# 10BASE-T1L_3.net
KiCad netlist of a schematic drawn in EAGLE
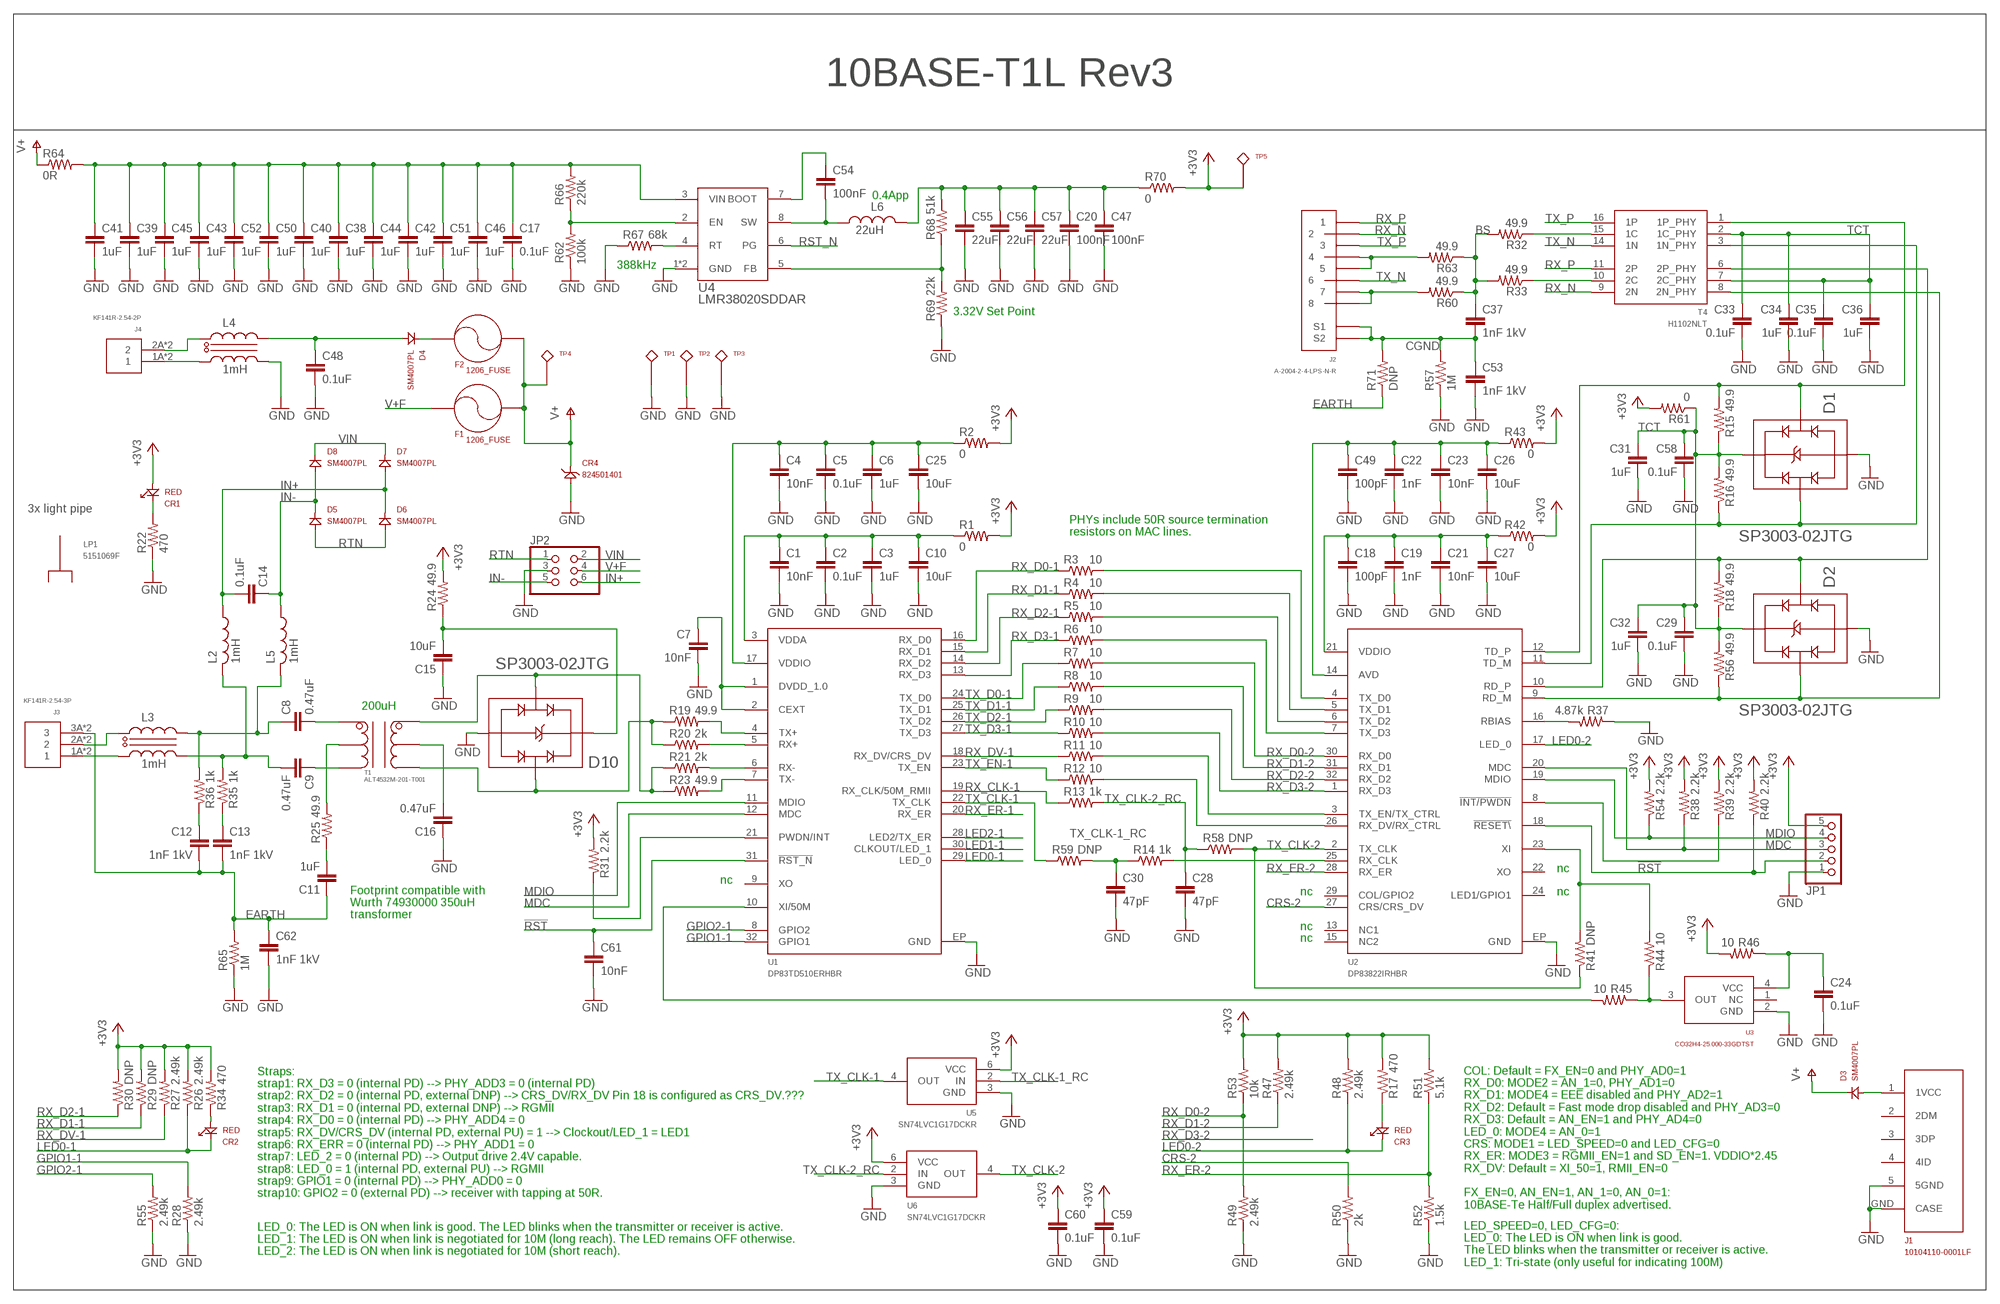
[diagram p0: schematic, sheet 1]

(export (version "E")
  (design (tool "Eeschema 10.0.6"))
  (components
    (comp (ref "C1")
      (value "10nF")
      (footprint "eagle-import:0402_INDUCTOR")
      (libsource (lib "eagle-import") (part "0402_CAPACITOR"))
    )
    (comp (ref "C2")
      (value "0.1uF")
      (footprint "eagle-import:0402_INDUCTOR")
      (libsource (lib "eagle-import") (part "0402_CAPACITOR"))
    )
    (comp (ref "C3")
      (value "1uF")
      (footprint "eagle-import:0402_INDUCTOR")
      (libsource (lib "eagle-import") (part "0402_CAPACITOR"))
    )
    (comp (ref "C4")
      (value "10nF")
      (footprint "eagle-import:0402_INDUCTOR")
      (libsource (lib "eagle-import") (part "0402_CAPACITOR"))
    )
    (comp (ref "C5")
      (value "0.1uF")
      (footprint "eagle-import:0402_INDUCTOR")
      (libsource (lib "eagle-import") (part "0402_CAPACITOR"))
    )
    (comp (ref "C6")
      (value "1uF")
      (footprint "eagle-import:0402_INDUCTOR")
      (libsource (lib "eagle-import") (part "0402_CAPACITOR"))
    )
    (comp (ref "C7")
      (value "10nF")
      (footprint "eagle-import:0402_INDUCTOR")
      (libsource (lib "eagle-import") (part "0402_CAPACITOR"))
    )
    (comp (ref "C8")
      (value "0.47uF")
      (footprint "eagle-import:0603")
      (libsource (lib "eagle-import") (part "0603_CAPACITOR"))
    )
    (comp (ref "C9")
      (value "0.47uF")
      (footprint "eagle-import:0603")
      (libsource (lib "eagle-import") (part "0603_CAPACITOR"))
    )
    (comp (ref "C10")
      (value "10uF")
      (footprint "eagle-import:0603")
      (libsource (lib "eagle-import") (part "0603_CAPACITOR"))
    )
    (comp (ref "C11")
      (value "1uF")
      (footprint "eagle-import:0603")
      (libsource (lib "eagle-import") (part "0603_CAPACITOR"))
    )
    (comp (ref "C12")
      (value "1nF 1kV")
      (footprint "eagle-import:C1206")
      (libsource (lib "eagle-import") (part "C-EUC1206"))
    )
    (comp (ref "C13")
      (value "1nF 1kV")
      (footprint "eagle-import:C1206")
      (libsource (lib "eagle-import") (part "C-EUC1206"))
    )
    (comp (ref "C14")
      (value "0.1uF")
      (footprint "eagle-import:0603")
      (libsource (lib "eagle-import") (part "0603_CAPACITOR"))
    )
    (comp (ref "C15")
      (value "10uF")
      (footprint "eagle-import:0603")
      (libsource (lib "eagle-import") (part "0603_CAPACITOR"))
    )
    (comp (ref "C16")
      (value "0.47uF")
      (footprint "eagle-import:0603")
      (libsource (lib "eagle-import") (part "0603_CAPACITOR"))
    )
    (comp (ref "C17")
      (value "0.1uF")
      (footprint "eagle-import:0603")
      (libsource (lib "eagle-import") (part "0603_CAPACITOR"))
    )
    (comp (ref "C18")
      (value "100pF")
      (footprint "eagle-import:0402_INDUCTOR")
      (libsource (lib "eagle-import") (part "0402_CAPACITOR"))
    )
    (comp (ref "C19")
      (value "1nF")
      (footprint "eagle-import:0402_INDUCTOR")
      (libsource (lib "eagle-import") (part "0402_CAPACITOR"))
    )
    (comp (ref "C20")
      (value "100nF")
      (footprint "eagle-import:0603")
      (libsource (lib "eagle-import") (part "0603_CAPACITOR"))
    )
    (comp (ref "C21")
      (value "10nF")
      (footprint "eagle-import:0402_INDUCTOR")
      (libsource (lib "eagle-import") (part "0402_CAPACITOR"))
    )
    (comp (ref "C22")
      (value "1nF")
      (footprint "eagle-import:0402_INDUCTOR")
      (libsource (lib "eagle-import") (part "0402_CAPACITOR"))
    )
    (comp (ref "C23")
      (value "10nF")
      (footprint "eagle-import:0402_INDUCTOR")
      (libsource (lib "eagle-import") (part "0402_CAPACITOR"))
    )
    (comp (ref "C24")
      (value "0.1uF")
      (footprint "eagle-import:0402_INDUCTOR")
      (libsource (lib "eagle-import") (part "0402_CAPACITOR"))
    )
    (comp (ref "C25")
      (value "10uF")
      (footprint "eagle-import:0603")
      (libsource (lib "eagle-import") (part "0603_CAPACITOR"))
    )
    (comp (ref "C26")
      (value "10uF")
      (footprint "eagle-import:0603")
      (libsource (lib "eagle-import") (part "0603_CAPACITOR"))
    )
    (comp (ref "C27")
      (value "10uF")
      (footprint "eagle-import:0603")
      (libsource (lib "eagle-import") (part "0603_CAPACITOR"))
    )
    (comp (ref "C28")
      (value "47pF")
      (footprint "eagle-import:0402_INDUCTOR")
      (libsource (lib "eagle-import") (part "0402_CAPACITOR"))
    )
    (comp (ref "C29")
      (value "0.1uF")
      (footprint "eagle-import:0402_INDUCTOR")
      (libsource (lib "eagle-import") (part "0402_CAPACITOR"))
    )
    (comp (ref "C30")
      (value "47pF")
      (footprint "eagle-import:0402_INDUCTOR")
      (libsource (lib "eagle-import") (part "0402_CAPACITOR"))
    )
    (comp (ref "C31")
      (value "1uF")
      (footprint "eagle-import:0402_INDUCTOR")
      (libsource (lib "eagle-import") (part "0402_CAPACITOR"))
    )
    (comp (ref "C32")
      (value "1uF")
      (footprint "eagle-import:0402_INDUCTOR")
      (libsource (lib "eagle-import") (part "0402_CAPACITOR"))
    )
    (comp (ref "C33")
      (value "0.1uF")
      (footprint "eagle-import:0402_INDUCTOR")
      (libsource (lib "eagle-import") (part "0402_CAPACITOR"))
    )
    (comp (ref "C34")
      (value "1uF")
      (footprint "eagle-import:0402_INDUCTOR")
      (libsource (lib "eagle-import") (part "0402_CAPACITOR"))
    )
    (comp (ref "C35")
      (value "0.1uF")
      (footprint "eagle-import:0402_INDUCTOR")
      (libsource (lib "eagle-import") (part "0402_CAPACITOR"))
    )
    (comp (ref "C36")
      (value "1uF")
      (footprint "eagle-import:0402_INDUCTOR")
      (libsource (lib "eagle-import") (part "0402_CAPACITOR"))
    )
    (comp (ref "C37")
      (value "1nF 1kV")
      (footprint "eagle-import:C1206")
      (libsource (lib "eagle-import") (part "C-EUC1206"))
    )
    (comp (ref "C38")
      (value "1uF")
      (footprint "eagle-import:C1206")
      (libsource (lib "eagle-import") (part "C-EUC1206"))
    )
    (comp (ref "C39")
      (value "1uF")
      (footprint "eagle-import:C1206")
      (libsource (lib "eagle-import") (part "C-EUC1206"))
    )
    (comp (ref "C40")
      (value "1uF")
      (footprint "eagle-import:C1206")
      (libsource (lib "eagle-import") (part "C-EUC1206"))
    )
    (comp (ref "C41")
      (value "1uF")
      (footprint "eagle-import:C1206")
      (libsource (lib "eagle-import") (part "C-EUC1206"))
    )
    (comp (ref "C42")
      (value "1uF")
      (footprint "eagle-import:C1206")
      (libsource (lib "eagle-import") (part "C-EUC1206"))
    )
    (comp (ref "C43")
      (value "1uF")
      (footprint "eagle-import:C1206")
      (libsource (lib "eagle-import") (part "C-EUC1206"))
    )
    (comp (ref "C44")
      (value "1uF")
      (footprint "eagle-import:C1206")
      (libsource (lib "eagle-import") (part "C-EUC1206"))
    )
    (comp (ref "C45")
      (value "1uF")
      (footprint "eagle-import:C1206")
      (libsource (lib "eagle-import") (part "C-EUC1206"))
    )
    (comp (ref "C46")
      (value "1uF")
      (footprint "eagle-import:C1206")
      (libsource (lib "eagle-import") (part "C-EUC1206"))
    )
    (comp (ref "C47")
      (value "100nF")
      (footprint "eagle-import:0603")
      (libsource (lib "eagle-import") (part "0603_CAPACITOR"))
    )
    (comp (ref "C48")
      (value "0.1uF")
      (footprint "eagle-import:0603")
      (libsource (lib "eagle-import") (part "0603_CAPACITOR"))
    )
    (comp (ref "C49")
      (value "100pF")
      (footprint "eagle-import:0402_INDUCTOR")
      (libsource (lib "eagle-import") (part "0402_CAPACITOR"))
    )
    (comp (ref "C50")
      (value "1uF")
      (footprint "eagle-import:C1206")
      (libsource (lib "eagle-import") (part "C-EUC1206"))
    )
    (comp (ref "C51")
      (value "1uF")
      (footprint "eagle-import:C1206")
      (libsource (lib "eagle-import") (part "C-EUC1206"))
    )
    (comp (ref "C52")
      (value "1uF")
      (footprint "eagle-import:C1206")
      (libsource (lib "eagle-import") (part "C-EUC1206"))
    )
    (comp (ref "C53")
      (value "1nF 1kV")
      (footprint "eagle-import:C1206")
      (libsource (lib "eagle-import") (part "C-EUC1206"))
    )
    (comp (ref "C54")
      (value "100nF")
      (footprint "eagle-import:0603")
      (libsource (lib "eagle-import") (part "0603_CAPACITOR"))
    )
    (comp (ref "C55")
      (value "22uF")
      (footprint "eagle-import:C1206")
      (libsource (lib "eagle-import") (part "C-EUC1206"))
    )
    (comp (ref "C56")
      (value "22uF")
      (footprint "eagle-import:C1206")
      (libsource (lib "eagle-import") (part "C-EUC1206"))
    )
    (comp (ref "C57")
      (value "22uF")
      (footprint "eagle-import:C1206")
      (libsource (lib "eagle-import") (part "C-EUC1206"))
    )
    (comp (ref "C58")
      (value "0.1uF")
      (footprint "eagle-import:0402_INDUCTOR")
      (libsource (lib "eagle-import") (part "0402_CAPACITOR"))
    )
    (comp (ref "C59")
      (value "0.1uF")
      (footprint "eagle-import:0402_INDUCTOR")
      (libsource (lib "eagle-import") (part "0402_CAPACITOR"))
    )
    (comp (ref "C60")
      (value "0.1uF")
      (footprint "eagle-import:0402_INDUCTOR")
      (libsource (lib "eagle-import") (part "0402_CAPACITOR"))
    )
    (comp (ref "C61")
      (value "10nF")
      (footprint "eagle-import:0402_INDUCTOR")
      (libsource (lib "eagle-import") (part "0402_CAPACITOR"))
    )
    (comp (ref "C62")
      (value "1nF 1kV")
      (footprint "eagle-import:C1206")
      (libsource (lib "eagle-import") (part "C-EUC1206"))
    )
    (comp (ref "CR1")
      (value "RED")
      (footprint "eagle-import:0603_DIODE")
      (fields (field (name "PARTNO") "732-4978-1-ND"))
      (libsource (lib "eagle-import") (part "150060RS75000"))
    )
    (comp (ref "CR2")
      (value "RED")
      (footprint "eagle-import:0603_DIODE")
      (fields (field (name "PARTNO") "732-4978-1-ND"))
      (libsource (lib "eagle-import") (part "150060RS75000"))
    )
    (comp (ref "CR3")
      (value "RED")
      (footprint "eagle-import:0603_DIODE")
      (fields (field (name "PARTNO") "732-4978-1-ND"))
      (libsource (lib "eagle-import") (part "150060RS75000"))
    )
    (comp (ref "CR4")
      (value "824501401")
      (footprint "eagle-import:DO-214AC")
      (fields (field (name "PARTNO") "732-9960-1-ND"))
      (libsource (lib "eagle-import") (part "824501401"))
    )
    (comp (ref "D1")
      (value "SP3003-02JTG")
      (footprint "eagle-import:SC-70-5")
      (fields (field (name "PARTNO") "F3301CT-ND"))
      (libsource (lib "eagle-import") (part "SP3003-02JTG"))
    )
    (comp (ref "D2")
      (value "SP3003-02JTG")
      (footprint "eagle-import:SC-70-5")
      (fields (field (name "PARTNO") "F3301CT-ND"))
      (libsource (lib "eagle-import") (part "SP3003-02JTG"))
    )
    (comp (ref "D3")
      (value "SM4007PL")
      (footprint "eagle-import:SOD123(AK)")
      (libsource (lib "eagle-import") (part "SM4007PL"))
    )
    (comp (ref "D4")
      (value "SM4007PL")
      (footprint "eagle-import:SOD123(AK)")
      (libsource (lib "eagle-import") (part "SM4007PL"))
    )
    (comp (ref "D5")
      (value "SM4007PL")
      (footprint "eagle-import:SOD123(AK)")
      (libsource (lib "eagle-import") (part "SM4007PL"))
    )
    (comp (ref "D6")
      (value "SM4007PL")
      (footprint "eagle-import:SOD123(AK)")
      (libsource (lib "eagle-import") (part "SM4007PL"))
    )
    (comp (ref "D7")
      (value "SM4007PL")
      (footprint "eagle-import:SOD123(AK)")
      (libsource (lib "eagle-import") (part "SM4007PL"))
    )
    (comp (ref "D8")
      (value "SM4007PL")
      (footprint "eagle-import:SOD123(AK)")
      (libsource (lib "eagle-import") (part "SM4007PL"))
    )
    (comp (ref "D10")
      (value "SP3003-02JTG")
      (footprint "eagle-import:SC-70-5")
      (fields (field (name "PARTNO") "F3301CT-ND"))
      (libsource (lib "eagle-import") (part "SP3003-02JTG"))
    )
    (comp (ref "F1")
      (value "1206_FUSE")
      (footprint "eagle-import:1206")
      (libsource (lib "eagle-import") (part "1206_FUSE"))
    )
    (comp (ref "F2")
      (value "1206_FUSE")
      (footprint "eagle-import:1206")
      (libsource (lib "eagle-import") (part "1206_FUSE"))
    )
    (comp (ref "J1")
      (value "10104110-0001LF")
      (footprint "eagle-import:MICRO_USB")
      (fields (field (name "PARTNO") "609-4052-1-ND"))
      (libsource (lib "eagle-import") (part "10104110-0001LF"))
    )
    (comp (ref "J2")
      (value "A-2004-2-4-LPS-N-R")
      (footprint "eagle-import:A-2004-2-4-LPS-N-R")
      (fields (field (name "PARTNO") "AE10387-ND"))
      (libsource (lib "eagle-import") (part "A-2004-2-4-LPS-N-R"))
    )
    (comp (ref "J3")
      (value "KF141R-2.54-3P")
      (footprint "eagle-import:KF141R-2.54-3P")
      (libsource (lib "eagle-import") (part "KF141R-2.54-3P"))
    )
    (comp (ref "J4")
      (value "KF141R-2.54-2P")
      (footprint "eagle-import:KF141R-2.54-2P")
      (libsource (lib "eagle-import") (part "KF141R-2.54-2P"))
    )
    (comp (ref "JP1")
      (value "PINHD-1X5")
      (footprint "eagle-import:1X05")
      (libsource (lib "eagle-import") (part "PINHD-1X5"))
    )
    (comp (ref "JP2")
      (value "PINHD-2X3")
      (footprint "eagle-import:2X03")
      (libsource (lib "eagle-import") (part "PINHD-2X3"))
    )
    (comp (ref "L2")
      (value "1mH")
      (footprint "eagle-import:SNR5040")
      (libsource (lib "eagle-import") (part "SNR5040TYD102M"))
    )
    (comp (ref "L3")
      (value "1mH")
      (footprint "eagle-import:SMCM090605")
      (libsource (lib "eagle-import") (part "SMCM090605-102"))
    )
    (comp (ref "L4")
      (value "1mH")
      (footprint "eagle-import:SMCM090605")
      (libsource (lib "eagle-import") (part "SMCM090605-102"))
    )
    (comp (ref "L5")
      (value "1mH")
      (footprint "eagle-import:SNR5040")
      (libsource (lib "eagle-import") (part "SNR5040TYD102M"))
    )
    (comp (ref "L6")
      (value "22uH")
      (footprint "eagle-import:TMPC0603H")
      (libsource (lib "eagle-import") (part "TMPC0603H-220MG-D"))
    )
    (comp (ref "LP1")
      (value "5151069F")
      (footprint "eagle-import:5151069F")
      (fields (field (name "PARTNO") "350-2182-ND"))
      (libsource (lib "eagle-import") (part "5151069F"))
    )
    (comp (ref "R1")
      (value "0")
      (footprint "eagle-import:0603")
      (libsource (lib "eagle-import") (part "0603_RESISTOR"))
    )
    (comp (ref "R2")
      (value "0")
      (footprint "eagle-import:0603")
      (libsource (lib "eagle-import") (part "0603_RESISTOR"))
    )
    (comp (ref "R3")
      (value "10")
      (footprint "eagle-import:R0402")
      (libsource (lib "eagle-import") (part "0402_RESISTOR"))
    )
    (comp (ref "R4")
      (value "10")
      (footprint "eagle-import:R0402")
      (libsource (lib "eagle-import") (part "0402_RESISTOR"))
    )
    (comp (ref "R5")
      (value "10")
      (footprint "eagle-import:R0402")
      (libsource (lib "eagle-import") (part "0402_RESISTOR"))
    )
    (comp (ref "R6")
      (value "10")
      (footprint "eagle-import:R0402")
      (libsource (lib "eagle-import") (part "0402_RESISTOR"))
    )
    (comp (ref "R7")
      (value "10")
      (footprint "eagle-import:R0402")
      (libsource (lib "eagle-import") (part "0402_RESISTOR"))
    )
    (comp (ref "R8")
      (value "10")
      (footprint "eagle-import:R0402")
      (libsource (lib "eagle-import") (part "0402_RESISTOR"))
    )
    (comp (ref "R9")
      (value "10")
      (footprint "eagle-import:R0402")
      (libsource (lib "eagle-import") (part "0402_RESISTOR"))
    )
    (comp (ref "R10")
      (value "10")
      (footprint "eagle-import:R0402")
      (libsource (lib "eagle-import") (part "0402_RESISTOR"))
    )
    (comp (ref "R11")
      (value "10")
      (footprint "eagle-import:R0402")
      (libsource (lib "eagle-import") (part "0402_RESISTOR"))
    )
    (comp (ref "R12")
      (value "10")
      (footprint "eagle-import:R0402")
      (libsource (lib "eagle-import") (part "0402_RESISTOR"))
    )
    (comp (ref "R13")
      (value "1k")
      (footprint "eagle-import:R0402")
      (libsource (lib "eagle-import") (part "0402_RESISTOR"))
    )
    (comp (ref "R14")
      (value "1k")
      (footprint "eagle-import:R0402")
      (libsource (lib "eagle-import") (part "0402_RESISTOR"))
    )
    (comp (ref "R15")
      (value "49.9")
      (footprint "eagle-import:R0402")
      (libsource (lib "eagle-import") (part "0402_RESISTOR"))
    )
    (comp (ref "R16")
      (value "49.9")
      (footprint "eagle-import:R0402")
      (libsource (lib "eagle-import") (part "0402_RESISTOR"))
    )
    (comp (ref "R17")
      (value "470")
      (footprint "eagle-import:0603")
      (libsource (lib "eagle-import") (part "0603_RESISTOR"))
    )
    (comp (ref "R18")
      (value "49.9")
      (footprint "eagle-import:R0402")
      (libsource (lib "eagle-import") (part "0402_RESISTOR"))
    )
    (comp (ref "R19")
      (value "49.9")
      (footprint "eagle-import:R0402")
      (libsource (lib "eagle-import") (part "0402_RESISTOR"))
    )
    (comp (ref "R20")
      (value "2k")
      (footprint "eagle-import:R0402")
      (libsource (lib "eagle-import") (part "0402_RESISTOR"))
    )
    (comp (ref "R21")
      (value "2k")
      (footprint "eagle-import:R0402")
      (libsource (lib "eagle-import") (part "0402_RESISTOR"))
    )
    (comp (ref "R22")
      (value "470")
      (footprint "eagle-import:0603")
      (libsource (lib "eagle-import") (part "0603_RESISTOR"))
    )
    (comp (ref "R23")
      (value "49.9")
      (footprint "eagle-import:R0402")
      (libsource (lib "eagle-import") (part "0402_RESISTOR"))
    )
    (comp (ref "R24")
      (value "49.9")
      (footprint "eagle-import:0603")
      (libsource (lib "eagle-import") (part "0603_RESISTOR"))
    )
    (comp (ref "R25")
      (value "49.9")
      (footprint "eagle-import:0603")
      (libsource (lib "eagle-import") (part "0603_RESISTOR"))
    )
    (comp (ref "R26")
      (value "2.49k")
      (footprint "eagle-import:R0402")
      (libsource (lib "eagle-import") (part "0402_RESISTOR"))
    )
    (comp (ref "R27")
      (value "2.49k")
      (footprint "eagle-import:R0402")
      (libsource (lib "eagle-import") (part "0402_RESISTOR"))
    )
    (comp (ref "R28")
      (value "2.49k")
      (footprint "eagle-import:R0402")
      (libsource (lib "eagle-import") (part "0402_RESISTOR"))
    )
    (comp (ref "R29")
      (value "DNP")
      (footprint "eagle-import:R0402")
      (libsource (lib "eagle-import") (part "0402_RESISTOR"))
    )
    (comp (ref "R30")
      (value "DNP")
      (footprint "eagle-import:R0402")
      (libsource (lib "eagle-import") (part "0402_RESISTOR"))
    )
    (comp (ref "R31")
      (value "2.2k")
      (footprint "eagle-import:R0402")
      (libsource (lib "eagle-import") (part "0402_RESISTOR"))
    )
    (comp (ref "R32")
      (value "49.9")
      (footprint "eagle-import:R0402")
      (libsource (lib "eagle-import") (part "0402_RESISTOR"))
    )
    (comp (ref "R33")
      (value "49.9")
      (footprint "eagle-import:R0402")
      (libsource (lib "eagle-import") (part "0402_RESISTOR"))
    )
    (comp (ref "R34")
      (value "470")
      (footprint "eagle-import:0603")
      (libsource (lib "eagle-import") (part "0603_RESISTOR"))
    )
    (comp (ref "R35")
      (value "1k")
      (footprint "eagle-import:0603")
      (libsource (lib "eagle-import") (part "0603_RESISTOR"))
    )
    (comp (ref "R36")
      (value "1k")
      (footprint "eagle-import:0603")
      (libsource (lib "eagle-import") (part "0603_RESISTOR"))
    )
    (comp (ref "R37")
      (value "4.87k")
      (footprint "eagle-import:R0402")
      (libsource (lib "eagle-import") (part "0402_RESISTOR"))
    )
    (comp (ref "R38")
      (value "2.2k")
      (footprint "eagle-import:R0402")
      (libsource (lib "eagle-import") (part "0402_RESISTOR"))
    )
    (comp (ref "R39")
      (value "2.2k")
      (footprint "eagle-import:R0402")
      (libsource (lib "eagle-import") (part "0402_RESISTOR"))
    )
    (comp (ref "R40")
      (value "2.2k")
      (footprint "eagle-import:R0402")
      (libsource (lib "eagle-import") (part "0402_RESISTOR"))
    )
    (comp (ref "R41")
      (value "DNP")
      (footprint "eagle-import:R0402")
      (libsource (lib "eagle-import") (part "0402_RESISTOR"))
    )
    (comp (ref "R42")
      (value "0")
      (footprint "eagle-import:0603")
      (libsource (lib "eagle-import") (part "0603_RESISTOR"))
    )
    (comp (ref "R43")
      (value "0")
      (footprint "eagle-import:0603")
      (libsource (lib "eagle-import") (part "0603_RESISTOR"))
    )
    (comp (ref "R44")
      (value "10")
      (footprint "eagle-import:R0402")
      (libsource (lib "eagle-import") (part "0402_RESISTOR"))
    )
    (comp (ref "R45")
      (value "10")
      (footprint "eagle-import:R0402")
      (libsource (lib "eagle-import") (part "0402_RESISTOR"))
    )
    (comp (ref "R46")
      (value "10")
      (footprint "eagle-import:R0402")
      (libsource (lib "eagle-import") (part "0402_RESISTOR"))
    )
    (comp (ref "R47")
      (value "2.49k")
      (footprint "eagle-import:R0402")
      (libsource (lib "eagle-import") (part "0402_RESISTOR"))
    )
    (comp (ref "R48")
      (value "2.49k")
      (footprint "eagle-import:R0402")
      (libsource (lib "eagle-import") (part "0402_RESISTOR"))
    )
    (comp (ref "R49")
      (value "2.49k")
      (footprint "eagle-import:R0402")
      (libsource (lib "eagle-import") (part "0402_RESISTOR"))
    )
    (comp (ref "R50")
      (value "2k")
      (footprint "eagle-import:R0402")
      (libsource (lib "eagle-import") (part "0402_RESISTOR"))
    )
    (comp (ref "R51")
      (value "5.1k")
      (footprint "eagle-import:R0402")
      (libsource (lib "eagle-import") (part "0402_RESISTOR"))
    )
    (comp (ref "R52")
      (value "1.5k")
      (footprint "eagle-import:R0402")
      (libsource (lib "eagle-import") (part "0402_RESISTOR"))
    )
    (comp (ref "R53")
      (value "10k")
      (footprint "eagle-import:R0402")
      (libsource (lib "eagle-import") (part "0402_RESISTOR"))
    )
    (comp (ref "R54")
      (value "2.2k")
      (footprint "eagle-import:R0402")
      (libsource (lib "eagle-import") (part "0402_RESISTOR"))
    )
    (comp (ref "R55")
      (value "2.49k")
      (footprint "eagle-import:R0402")
      (libsource (lib "eagle-import") (part "0402_RESISTOR"))
    )
    (comp (ref "R56")
      (value "49.9")
      (footprint "eagle-import:R0402")
      (libsource (lib "eagle-import") (part "0402_RESISTOR"))
    )
    (comp (ref "R57")
      (value "1M")
      (footprint "eagle-import:1206")
      (libsource (lib "eagle-import") (part "1206_RESISTOR"))
    )
    (comp (ref "R58")
      (value "DNP")
      (footprint "eagle-import:R0402")
      (libsource (lib "eagle-import") (part "0402_RESISTOR"))
    )
    (comp (ref "R59")
      (value "DNP")
      (footprint "eagle-import:R0402")
      (libsource (lib "eagle-import") (part "0402_RESISTOR"))
    )
    (comp (ref "R60")
      (value "49.9")
      (footprint "eagle-import:R0402")
      (libsource (lib "eagle-import") (part "0402_RESISTOR"))
    )
    (comp (ref "R61")
      (value "0")
      (footprint "eagle-import:0603")
      (libsource (lib "eagle-import") (part "0603_RESISTOR"))
    )
    (comp (ref "R62")
      (value "100k")
      (footprint "eagle-import:0603")
      (libsource (lib "eagle-import") (part "0603_RESISTOR"))
    )
    (comp (ref "R63")
      (value "49.9")
      (footprint "eagle-import:R0402")
      (libsource (lib "eagle-import") (part "0402_RESISTOR"))
    )
    (comp (ref "R64")
      (value "0R")
      (footprint "eagle-import:1206")
      (libsource (lib "eagle-import") (part "1206_RESISTOR"))
    )
    (comp (ref "R65")
      (value "1M")
      (footprint "eagle-import:1206")
      (libsource (lib "eagle-import") (part "1206_RESISTOR"))
    )
    (comp (ref "R66")
      (value "220k")
      (footprint "eagle-import:0603")
      (libsource (lib "eagle-import") (part "0603_RESISTOR"))
    )
    (comp (ref "R67")
      (value "68k")
      (footprint "eagle-import:0603")
      (libsource (lib "eagle-import") (part "0603_RESISTOR"))
    )
    (comp (ref "R68")
      (value "51k")
      (footprint "eagle-import:0603")
      (libsource (lib "eagle-import") (part "0603_RESISTOR"))
    )
    (comp (ref "R69")
      (value "22k")
      (footprint "eagle-import:0603")
      (libsource (lib "eagle-import") (part "0603_RESISTOR"))
    )
    (comp (ref "R70")
      (value "0")
      (footprint "eagle-import:0603")
      (libsource (lib "eagle-import") (part "0603_RESISTOR"))
    )
    (comp (ref "R71")
      (value "DNP")
      (footprint "eagle-import:0603")
      (libsource (lib "eagle-import") (part "0603_RESISTOR"))
    )
    (comp (ref "T1")
      (value "ALT4532M-201-T001")
      (footprint "eagle-import:TDK_ALT")
      (fields (field (name "PARTNO") "445-15085-1-ND"))
      (libsource (lib "eagle-import") (part "ALT4532M-201-T001"))
    )
    (comp (ref "T4")
      (value "H1102NLT")
      (footprint "eagle-import:H1102NLT")
      (libsource (lib "eagle-import") (part "H1102NLT"))
    )
    (comp (ref "TP1")
      (value "5011")
      (footprint "eagle-import:5010")
      (fields (field (name "PARTNO") "36-5011-ND"))
      (libsource (lib "eagle-import") (part "5011"))
    )
    (comp (ref "TP2")
      (value "5011")
      (footprint "eagle-import:5010")
      (fields (field (name "PARTNO") "36-5011-ND"))
      (libsource (lib "eagle-import") (part "5011"))
    )
    (comp (ref "TP3")
      (value "5011")
      (footprint "eagle-import:5010")
      (fields (field (name "PARTNO") "36-5011-ND"))
      (libsource (lib "eagle-import") (part "5011"))
    )
    (comp (ref "TP4")
      (value "5010")
      (footprint "eagle-import:5010")
      (fields (field (name "PARTNO") "36-5010-ND"))
      (libsource (lib "eagle-import") (part "5010"))
    )
    (comp (ref "TP5")
      (value "5010")
      (footprint "eagle-import:5010")
      (fields (field (name "PARTNO") "36-5010-ND"))
      (libsource (lib "eagle-import") (part "5010"))
    )
    (comp (ref "U1")
      (value "DP83TD510ERHBR")
      (footprint "eagle-import:QFN32-55_TI")
      (fields (field (name "PARTNO") "296-DP83TD510ERHBRCT-ND"))
      (libsource (lib "eagle-import") (part "DP83TD510ERHBR"))
    )
    (comp (ref "U2")
      (value "DP83822IRHBR")
      (footprint "eagle-import:QFN32-55_TI")
      (fields (field (name "PARTNO") "296-44794-1-ND"))
      (libsource (lib "eagle-import") (part "DP83822IRHBR"))
    )
    (comp (ref "U3")
      (value "CO32H4-25.000-33GDTST")
      (footprint "eagle-import:3.2X2.5_4SMD")
      (libsource (lib "eagle-import") (part "CO32H4-25.000-33GDTST"))
    )
    (comp (ref "U4")
      (value "LMR38020SDDAR")
      (footprint "eagle-import:SOIC8_TP_TI")
      (fields (field (name "PARTNO") "296-LMR38020SDDARCT-ND"))
      (libsource (lib "eagle-import") (part "LMR38020SDDAR"))
    )
    (comp (ref "U5")
      (value "SN74LVC1G17DCKR")
      (footprint "eagle-import:SC-70")
      (fields (field (name "PARTNO") "296-11934-1-ND"))
      (libsource (lib "eagle-import") (part "SN74LVC1G17DCKR"))
    )
    (comp (ref "U6")
      (value "SN74LVC1G17DCKR")
      (footprint "eagle-import:SC-70")
      (fields (field (name "PARTNO") "296-11934-1-ND"))
      (libsource (lib "eagle-import") (part "SN74LVC1G17DCKR"))
    )
  )
  (nets
    (net (code "1") (name "+3V3") (class "Default")
      (node (ref "C59") (pin "P$1") (pinfunction "1_P$1") (pintype "passive"))
      (node (ref "C60") (pin "P$1") (pinfunction "1_P$1") (pintype "passive"))
      (node (ref "CR1") (pin "A") (pinfunction "A_A") (pintype "bidirectional"))
      (node (ref "JP1") (pin "5") (pinfunction "5_5") (pintype "passive"))
      (node (ref "R1") (pin "2") (pinfunction "2_2") (pintype "passive"))
      (node (ref "R17") (pin "2") (pinfunction "2_2") (pintype "passive"))
      (node (ref "R2") (pin "2") (pinfunction "2_2") (pintype "passive"))
      (node (ref "R24") (pin "2") (pinfunction "2_2") (pintype "passive"))
      (node (ref "R26") (pin "2") (pinfunction "2_2") (pintype "passive"))
      (node (ref "R27") (pin "2") (pinfunction "2_2") (pintype "passive"))
      (node (ref "R29") (pin "2") (pinfunction "2_2") (pintype "passive"))
      (node (ref "R30") (pin "2") (pinfunction "2_2") (pintype "passive"))
      (node (ref "R31") (pin "2") (pinfunction "2_2") (pintype "passive"))
      (node (ref "R34") (pin "2") (pinfunction "2_2") (pintype "passive"))
      (node (ref "R38") (pin "2") (pinfunction "2_2") (pintype "passive"))
      (node (ref "R39") (pin "2") (pinfunction "2_2") (pintype "passive"))
      (node (ref "R40") (pin "2") (pinfunction "2_2") (pintype "passive"))
      (node (ref "R42") (pin "2") (pinfunction "2_2") (pintype "passive"))
      (node (ref "R43") (pin "2") (pinfunction "2_2") (pintype "passive"))
      (node (ref "R46") (pin "2") (pinfunction "2_2") (pintype "passive"))
      (node (ref "R47") (pin "2") (pinfunction "2_2") (pintype "passive"))
      (node (ref "R48") (pin "2") (pinfunction "2_2") (pintype "passive"))
      (node (ref "R51") (pin "2") (pinfunction "2_2") (pintype "passive"))
      (node (ref "R53") (pin "2") (pinfunction "2_2") (pintype "passive"))
      (node (ref "R54") (pin "2") (pinfunction "2_2") (pintype "passive"))
      (node (ref "R61") (pin "2") (pinfunction "2_2") (pintype "passive"))
      (node (ref "R70") (pin "2") (pinfunction "2_2") (pintype "passive"))
      (node (ref "TP5") (pin "P$1") (pinfunction "P$1_P$1") (pintype "bidirectional"))
      (node (ref "U5") (pin "6") (pinfunction "VCC_6") (pintype "bidirectional"))
      (node (ref "U6") (pin "6") (pinfunction "VCC_6") (pintype "bidirectional"))
    )
    (net (code "2") (name "BS") (class "Default")
      (node (ref "C37") (pin "1") (pinfunction "1_1") (pintype "passive"))
      (node (ref "R32") (pin "2") (pinfunction "2_2") (pintype "passive"))
      (node (ref "R33") (pin "2") (pinfunction "2_2") (pintype "passive"))
      (node (ref "R60") (pin "1") (pinfunction "1_1") (pintype "passive"))
      (node (ref "R63") (pin "1") (pinfunction "1_1") (pintype "passive"))
    )
    (net (code "3") (name "CGND") (class "Default")
      (node (ref "C37") (pin "2") (pinfunction "2_2") (pintype "passive"))
      (node (ref "C53") (pin "1") (pinfunction "1_1") (pintype "passive"))
      (node (ref "J2") (pin "S1") (pinfunction "S1_S1") (pintype "bidirectional"))
      (node (ref "J2") (pin "S2") (pinfunction "S2_S2") (pintype "bidirectional"))
      (node (ref "R57") (pin "2") (pinfunction "2_2") (pintype "passive"))
      (node (ref "R71") (pin "2") (pinfunction "2_2") (pintype "passive"))
    )
    (net (code "4") (name "CRS-2") (class "Default")
      (node (ref "R50") (pin "2") (pinfunction "2_2") (pintype "passive"))
      (node (ref "U2") (pin "27") (pinfunction "CRS/CRS_DV_27") (pintype "bidirectional"))
    )
    (net (code "5") (name "EARTH") (class "Default")
      (node (ref "C11") (pin "1") (pinfunction "1_1") (pintype "passive"))
      (node (ref "C12") (pin "2") (pinfunction "2_2") (pintype "passive"))
      (node (ref "C13") (pin "2") (pinfunction "2_2") (pintype "passive"))
      (node (ref "C62") (pin "1") (pinfunction "1_1") (pintype "passive"))
      (node (ref "J3") (pin "3A") (pinfunction "3_3A") (pintype "bidirectional"))
      (node (ref "J3") (pin "3B") (pinfunction "3_3B") (pintype "bidirectional"))
      (node (ref "R65") (pin "2") (pinfunction "2_2") (pintype "passive"))
      (node (ref "R71") (pin "1") (pinfunction "1_1") (pintype "passive"))
    )
    (net (code "6") (name "GND") (class "Default")
      (node (ref "C1") (pin "P$2") (pinfunction "2_P$2") (pintype "passive"))
      (node (ref "C10") (pin "2") (pinfunction "2_2") (pintype "passive"))
      (node (ref "C15") (pin "1") (pinfunction "1_1") (pintype "passive"))
      (node (ref "C16") (pin "1") (pinfunction "1_1") (pintype "passive"))
      (node (ref "C17") (pin "2") (pinfunction "2_2") (pintype "passive"))
      (node (ref "C18") (pin "P$2") (pinfunction "2_P$2") (pintype "passive"))
      (node (ref "C19") (pin "P$2") (pinfunction "2_P$2") (pintype "passive"))
      (node (ref "C2") (pin "P$2") (pinfunction "2_P$2") (pintype "passive"))
      (node (ref "C20") (pin "2") (pinfunction "2_2") (pintype "passive"))
      (node (ref "C21") (pin "P$2") (pinfunction "2_P$2") (pintype "passive"))
      (node (ref "C22") (pin "P$2") (pinfunction "2_P$2") (pintype "passive"))
      (node (ref "C23") (pin "P$2") (pinfunction "2_P$2") (pintype "passive"))
      (node (ref "C24") (pin "P$2") (pinfunction "2_P$2") (pintype "passive"))
      (node (ref "C25") (pin "2") (pinfunction "2_2") (pintype "passive"))
      (node (ref "C26") (pin "2") (pinfunction "2_2") (pintype "passive"))
      (node (ref "C27") (pin "2") (pinfunction "2_2") (pintype "passive"))
      (node (ref "C28") (pin "P$2") (pinfunction "2_P$2") (pintype "passive"))
      (node (ref "C29") (pin "P$2") (pinfunction "2_P$2") (pintype "passive"))
      (node (ref "C3") (pin "P$2") (pinfunction "2_P$2") (pintype "passive"))
      (node (ref "C30") (pin "P$2") (pinfunction "2_P$2") (pintype "passive"))
      (node (ref "C31") (pin "P$2") (pinfunction "2_P$2") (pintype "passive"))
      (node (ref "C32") (pin "P$2") (pinfunction "2_P$2") (pintype "passive"))
      (node (ref "C33") (pin "P$2") (pinfunction "2_P$2") (pintype "passive"))
      (node (ref "C34") (pin "P$2") (pinfunction "2_P$2") (pintype "passive"))
      (node (ref "C35") (pin "P$2") (pinfunction "2_P$2") (pintype "passive"))
      (node (ref "C36") (pin "P$2") (pinfunction "2_P$2") (pintype "passive"))
      (node (ref "C38") (pin "2") (pinfunction "2_2") (pintype "passive"))
      (node (ref "C39") (pin "2") (pinfunction "2_2") (pintype "passive"))
      (node (ref "C4") (pin "P$2") (pinfunction "2_P$2") (pintype "passive"))
      (node (ref "C40") (pin "2") (pinfunction "2_2") (pintype "passive"))
      (node (ref "C41") (pin "2") (pinfunction "2_2") (pintype "passive"))
      (node (ref "C42") (pin "2") (pinfunction "2_2") (pintype "passive"))
      (node (ref "C43") (pin "2") (pinfunction "2_2") (pintype "passive"))
      (node (ref "C44") (pin "2") (pinfunction "2_2") (pintype "passive"))
      (node (ref "C45") (pin "2") (pinfunction "2_2") (pintype "passive"))
      (node (ref "C46") (pin "2") (pinfunction "2_2") (pintype "passive"))
      (node (ref "C47") (pin "2") (pinfunction "2_2") (pintype "passive"))
      (node (ref "C48") (pin "2") (pinfunction "2_2") (pintype "passive"))
      (node (ref "C49") (pin "P$2") (pinfunction "2_P$2") (pintype "passive"))
      (node (ref "C5") (pin "P$2") (pinfunction "2_P$2") (pintype "passive"))
      (node (ref "C50") (pin "2") (pinfunction "2_2") (pintype "passive"))
      (node (ref "C51") (pin "2") (pinfunction "2_2") (pintype "passive"))
      (node (ref "C52") (pin "2") (pinfunction "2_2") (pintype "passive"))
      (node (ref "C53") (pin "2") (pinfunction "2_2") (pintype "passive"))
      (node (ref "C55") (pin "2") (pinfunction "2_2") (pintype "passive"))
      (node (ref "C56") (pin "2") (pinfunction "2_2") (pintype "passive"))
      (node (ref "C57") (pin "2") (pinfunction "2_2") (pintype "passive"))
      (node (ref "C58") (pin "P$2") (pinfunction "2_P$2") (pintype "passive"))
      (node (ref "C59") (pin "P$2") (pinfunction "2_P$2") (pintype "passive"))
      (node (ref "C6") (pin "P$2") (pinfunction "2_P$2") (pintype "passive"))
      (node (ref "C60") (pin "P$2") (pinfunction "2_P$2") (pintype "passive"))
      (node (ref "C61") (pin "P$2") (pinfunction "2_P$2") (pintype "passive"))
      (node (ref "C62") (pin "2") (pinfunction "2_2") (pintype "passive"))
      (node (ref "C7") (pin "P$2") (pinfunction "2_P$2") (pintype "passive"))
      (node (ref "CR4") (pin "A") (pinfunction "A_A") (pintype "bidirectional"))
      (node (ref "D1") (pin "2") (pinfunction "GND_2") (pintype "bidirectional"))
      (node (ref "D10") (pin "2") (pinfunction "GND_2") (pintype "bidirectional"))
      (node (ref "D2") (pin "2") (pinfunction "GND_2") (pintype "bidirectional"))
      (node (ref "J1") (pin "5") (pinfunction "5GND_5") (pintype "bidirectional"))
      (node (ref "J1") (pin "GND") (pinfunction "CASE_GND") (pintype "bidirectional"))
      (node (ref "JP1") (pin "1") (pinfunction "1_1") (pintype "passive"))
      (node (ref "JP2") (pin "3") (pinfunction "3_3") (pintype "passive"))
      (node (ref "L4") (pin "OUT2") (pinfunction "2OUT_OUT2") (pintype "bidirectional"))
      (node (ref "R22") (pin "1") (pinfunction "1_1") (pintype "passive"))
      (node (ref "R28") (pin "1") (pinfunction "1_1") (pintype "passive"))
      (node (ref "R37") (pin "1") (pinfunction "1_1") (pintype "passive"))
      (node (ref "R49") (pin "1") (pinfunction "1_1") (pintype "passive"))
      (node (ref "R50") (pin "1") (pinfunction "1_1") (pintype "passive"))
      (node (ref "R52") (pin "1") (pinfunction "1_1") (pintype "passive"))
      (node (ref "R55") (pin "1") (pinfunction "1_1") (pintype "passive"))
      (node (ref "R57") (pin "1") (pinfunction "1_1") (pintype "passive"))
      (node (ref "R62") (pin "1") (pinfunction "1_1") (pintype "passive"))
      (node (ref "R65") (pin "1") (pinfunction "1_1") (pintype "passive"))
      (node (ref "R67") (pin "1") (pinfunction "1_1") (pintype "passive"))
      (node (ref "R69") (pin "1") (pinfunction "1_1") (pintype "passive"))
      (node (ref "TP1") (pin "P$1") (pinfunction "P$1_P$1") (pintype "bidirectional"))
      (node (ref "TP2") (pin "P$1") (pinfunction "P$1_P$1") (pintype "bidirectional"))
      (node (ref "TP3") (pin "P$1") (pinfunction "P$1_P$1") (pintype "bidirectional"))
      (node (ref "U1") (pin "EP") (pinfunction "GND_EP") (pintype "bidirectional"))
      (node (ref "U2") (pin "EP") (pinfunction "GND_EP") (pintype "bidirectional"))
      (node (ref "U3") (pin "2") (pinfunction "GND_2") (pintype "bidirectional"))
      (node (ref "U4") (pin "1") (pinfunction "GND_1") (pintype "bidirectional"))
      (node (ref "U4") (pin "TP") (pinfunction "GND_TP") (pintype "bidirectional"))
      (node (ref "U5") (pin "3") (pinfunction "GND_3") (pintype "bidirectional"))
      (node (ref "U6") (pin "3") (pinfunction "GND_3") (pintype "bidirectional"))
    )
    (net (code "7") (name "GPIO1-1") (class "Default")
      (node (ref "R28") (pin "2") (pinfunction "2_2") (pintype "passive"))
      (node (ref "U1") (pin "32") (pinfunction "GPIO1_32") (pintype "bidirectional"))
    )
    (net (code "8") (name "GPIO2-1") (class "Default")
      (node (ref "R55") (pin "2") (pinfunction "2_2") (pintype "passive"))
      (node (ref "U1") (pin "8") (pinfunction "GPIO2_8") (pintype "bidirectional"))
    )
    (net (code "9") (name "IN+") (class "Default")
      (node (ref "C14") (pin "2") (pinfunction "2_2") (pintype "passive"))
      (node (ref "D6") (pin "K") (pinfunction "K_K") (pintype "bidirectional"))
      (node (ref "D7") (pin "A") (pinfunction "A_A") (pintype "bidirectional"))
      (node (ref "JP2") (pin "6") (pinfunction "6_6") (pintype "passive"))
      (node (ref "L2") (pin "P$1") (pinfunction "1_P$1") (pintype "passive"))
    )
    (net (code "10") (name "IN-") (class "Default")
      (node (ref "C14") (pin "1") (pinfunction "1_1") (pintype "passive"))
      (node (ref "D5") (pin "K") (pinfunction "K_K") (pintype "bidirectional"))
      (node (ref "D8") (pin "A") (pinfunction "A_A") (pintype "bidirectional"))
      (node (ref "JP2") (pin "5") (pinfunction "5_5") (pintype "passive"))
      (node (ref "L5") (pin "P$1") (pinfunction "1_P$1") (pintype "passive"))
    )
    (net (code "11") (name "LED0-1") (class "Default")
      (node (ref "CR2") (pin "K") (pinfunction "K_K") (pintype "bidirectional"))
      (node (ref "R26") (pin "1") (pinfunction "1_1") (pintype "passive"))
      (node (ref "U1") (pin "29") (pinfunction "LED_0_29") (pintype "bidirectional"))
    )
    (net (code "12") (name "LED0-2") (class "Default")
      (node (ref "CR3") (pin "K") (pinfunction "K_K") (pintype "bidirectional"))
      (node (ref "R48") (pin "1") (pinfunction "1_1") (pintype "passive"))
      (node (ref "U2") (pin "17") (pinfunction "LED_0_17") (pintype "bidirectional"))
    )
    (net (code "13") (name "LED1-1") (class "Default")
      (node (ref "U1") (pin "30") (pinfunction "CLKOUT/LED_1_30") (pintype "bidirectional"))
    )
    (net (code "14") (name "LED2-1") (class "Default")
      (node (ref "U1") (pin "28") (pinfunction "LED2/TX_ER_28") (pintype "bidirectional"))
    )
    (net (code "15") (name "MDC") (class "Default")
      (node (ref "JP1") (pin "3") (pinfunction "3_3") (pintype "passive"))
      (node (ref "R38") (pin "1") (pinfunction "1_1") (pintype "passive"))
      (node (ref "U1") (pin "12") (pinfunction "MDC_12") (pintype "bidirectional"))
      (node (ref "U2") (pin "20") (pinfunction "MDC_20") (pintype "bidirectional"))
    )
    (net (code "16") (name "MDIO") (class "Default")
      (node (ref "JP1") (pin "4") (pinfunction "4_4") (pintype "passive"))
      (node (ref "R54") (pin "1") (pinfunction "1_1") (pintype "passive"))
      (node (ref "U1") (pin "11") (pinfunction "MDIO_11") (pintype "bidirectional"))
      (node (ref "U2") (pin "19") (pinfunction "MDIO_19") (pintype "bidirectional"))
    )
    (net (code "17") (name "Net-(C1-1)") (class "Default")
      (node (ref "C1") (pin "P$1") (pinfunction "1_P$1") (pintype "passive"))
      (node (ref "C10") (pin "1") (pinfunction "1_1") (pintype "passive"))
      (node (ref "C2") (pin "P$1") (pinfunction "1_P$1") (pintype "passive"))
      (node (ref "C3") (pin "P$1") (pinfunction "1_P$1") (pintype "passive"))
      (node (ref "R1") (pin "1") (pinfunction "1_1") (pintype "passive"))
      (node (ref "U1") (pin "3") (pinfunction "VDDA_3") (pintype "bidirectional"))
    )
    (net (code "18") (name "Net-(C4-1)") (class "Default")
      (node (ref "C25") (pin "1") (pinfunction "1_1") (pintype "passive"))
      (node (ref "C4") (pin "P$1") (pinfunction "1_P$1") (pintype "passive"))
      (node (ref "C5") (pin "P$1") (pinfunction "1_P$1") (pintype "passive"))
      (node (ref "C6") (pin "P$1") (pinfunction "1_P$1") (pintype "passive"))
      (node (ref "R2") (pin "1") (pinfunction "1_1") (pintype "passive"))
      (node (ref "U1") (pin "17") (pinfunction "VDDIO_17") (pintype "bidirectional"))
    )
    (net (code "19") (name "Net-(C7-1)") (class "Default")
      (node (ref "C7") (pin "P$1") (pinfunction "1_P$1") (pintype "passive"))
      (node (ref "U1") (pin "1") (pinfunction "DVDD_1.0_1") (pintype "bidirectional"))
      (node (ref "U1") (pin "2") (pinfunction "CEXT_2") (pintype "bidirectional"))
    )
    (net (code "20") (name "Net-(C8-Pad2)") (class "Default")
      (node (ref "C8") (pin "2") (pinfunction "2_2") (pintype "passive"))
      (node (ref "T1") (pin "1") (pinfunction "1_1") (pintype "bidirectional"))
    )
    (net (code "21") (name "Net-(C11-Pad2)") (class "Default")
      (node (ref "C11") (pin "2") (pinfunction "2_2") (pintype "passive"))
      (node (ref "R25") (pin "1") (pinfunction "1_1") (pintype "passive"))
    )
    (net (code "22") (name "Net-(C12-Pad1)") (class "Default")
      (node (ref "C12") (pin "1") (pinfunction "1_1") (pintype "passive"))
      (node (ref "R36") (pin "1") (pinfunction "1_1") (pintype "passive"))
    )
    (net (code "23") (name "Net-(C13-Pad1)") (class "Default")
      (node (ref "C13") (pin "1") (pinfunction "1_1") (pintype "passive"))
      (node (ref "R35") (pin "1") (pinfunction "1_1") (pintype "passive"))
    )
    (net (code "24") (name "Net-(C18-1)") (class "Default")
      (node (ref "C18") (pin "P$1") (pinfunction "1_P$1") (pintype "passive"))
      (node (ref "C19") (pin "P$1") (pinfunction "1_P$1") (pintype "passive"))
      (node (ref "C21") (pin "P$1") (pinfunction "1_P$1") (pintype "passive"))
      (node (ref "C27") (pin "1") (pinfunction "1_1") (pintype "passive"))
      (node (ref "R42") (pin "1") (pinfunction "1_1") (pintype "passive"))
      (node (ref "U2") (pin "21") (pinfunction "VDDIO_21") (pintype "bidirectional"))
    )
    (net (code "25") (name "Net-(C20-Pad1)") (class "Default")
      (node (ref "C20") (pin "1") (pinfunction "1_1") (pintype "passive"))
      (node (ref "C47") (pin "1") (pinfunction "1_1") (pintype "passive"))
      (node (ref "C55") (pin "1") (pinfunction "1_1") (pintype "passive"))
      (node (ref "C56") (pin "1") (pinfunction "1_1") (pintype "passive"))
      (node (ref "C57") (pin "1") (pinfunction "1_1") (pintype "passive"))
      (node (ref "L6") (pin "P$1") (pinfunction "P$1_P$1") (pintype "bidirectional"))
      (node (ref "R68") (pin "2") (pinfunction "2_2") (pintype "passive"))
      (node (ref "R70") (pin "1") (pinfunction "1_1") (pintype "passive"))
    )
    (net (code "26") (name "Net-(C22-1)") (class "Default")
      (node (ref "C22") (pin "P$1") (pinfunction "1_P$1") (pintype "passive"))
      (node (ref "C23") (pin "P$1") (pinfunction "1_P$1") (pintype "passive"))
      (node (ref "C26") (pin "1") (pinfunction "1_1") (pintype "passive"))
      (node (ref "C49") (pin "P$1") (pinfunction "1_P$1") (pintype "passive"))
      (node (ref "R43") (pin "1") (pinfunction "1_1") (pintype "passive"))
      (node (ref "U2") (pin "14") (pinfunction "AVD_14") (pintype "bidirectional"))
    )
    (net (code "27") (name "Net-(C24-1)") (class "Default")
      (node (ref "C24") (pin "P$1") (pinfunction "1_P$1") (pintype "passive"))
      (node (ref "R46") (pin "1") (pinfunction "1_1") (pintype "passive"))
      (node (ref "U3") (pin "4") (pinfunction "VCC_4") (pintype "bidirectional"))
    )
    (net (code "28") (name "Net-(CR1-PadK)") (class "Default")
      (node (ref "CR1") (pin "K") (pinfunction "K_K") (pintype "bidirectional"))
      (node (ref "R22") (pin "2") (pinfunction "2_2") (pintype "passive"))
    )
    (net (code "29") (name "Net-(CR2-PadA)") (class "Default")
      (node (ref "CR2") (pin "A") (pinfunction "A_A") (pintype "bidirectional"))
      (node (ref "R34") (pin "1") (pinfunction "1_1") (pintype "passive"))
    )
    (net (code "30") (name "Net-(CR3-PadA)") (class "Default")
      (node (ref "CR3") (pin "A") (pinfunction "A_A") (pintype "bidirectional"))
      (node (ref "R17") (pin "1") (pinfunction "1_1") (pintype "passive"))
    )
    (net (code "31") (name "Net-(D1-IO1)") (class "Default")
      (node (ref "D1") (pin "5") (pinfunction "IO1_5") (pintype "bidirectional"))
      (node (ref "R16") (pin "1") (pinfunction "1_1") (pintype "passive"))
      (node (ref "T4") (pin "3") (pinfunction "1N_PHY_3") (pintype "bidirectional"))
      (node (ref "U2") (pin "11") (pinfunction "TD_M_11") (pintype "bidirectional"))
    )
    (net (code "32") (name "Net-(D1-IO2)") (class "Default")
      (node (ref "D1") (pin "4") (pinfunction "IO2_4") (pintype "bidirectional"))
      (node (ref "R15") (pin "2") (pinfunction "2_2") (pintype "passive"))
      (node (ref "T4") (pin "1") (pinfunction "1P_PHY_1") (pintype "bidirectional"))
      (node (ref "U2") (pin "12") (pinfunction "TD_P_12") (pintype "bidirectional"))
    )
    (net (code "33") (name "Net-(D2-IO1)") (class "Default")
      (node (ref "D2") (pin "5") (pinfunction "IO1_5") (pintype "bidirectional"))
      (node (ref "R56") (pin "1") (pinfunction "1_1") (pintype "passive"))
      (node (ref "T4") (pin "8") (pinfunction "2N_PHY_8") (pintype "bidirectional"))
      (node (ref "U2") (pin "9") (pinfunction "RD_M_9") (pintype "bidirectional"))
    )
    (net (code "34") (name "Net-(D2-IO2)") (class "Default")
      (node (ref "D2") (pin "4") (pinfunction "IO2_4") (pintype "bidirectional"))
      (node (ref "R18") (pin "2") (pinfunction "2_2") (pintype "passive"))
      (node (ref "T4") (pin "6") (pinfunction "2P_PHY_6") (pintype "bidirectional"))
      (node (ref "U2") (pin "10") (pinfunction "RD_P_10") (pintype "bidirectional"))
    )
    (net (code "35") (name "Net-(D10-IO1)") (class "Default")
      (node (ref "D10") (pin "5") (pinfunction "IO1_5") (pintype "bidirectional"))
      (node (ref "R21") (pin "1") (pinfunction "1_1") (pintype "passive"))
      (node (ref "R23") (pin "1") (pinfunction "1_1") (pintype "passive"))
      (node (ref "T1") (pin "5") (pinfunction "6_5") (pintype "bidirectional"))
    )
    (net (code "36") (name "Net-(D10-IO2)") (class "Default")
      (node (ref "D10") (pin "4") (pinfunction "IO2_4") (pintype "bidirectional"))
      (node (ref "R19") (pin "1") (pinfunction "1_1") (pintype "passive"))
      (node (ref "R20") (pin "1") (pinfunction "1_1") (pintype "passive"))
      (node (ref "T1") (pin "4") (pinfunction "4_4") (pintype "bidirectional"))
    )
    (net (code "37") (name "Net-(D10-VCC)") (class "Default")
      (node (ref "C15") (pin "2") (pinfunction "2_2") (pintype "passive"))
      (node (ref "D10") (pin "3") (pinfunction "VCC_3") (pintype "bidirectional"))
      (node (ref "R24") (pin "1") (pinfunction "1_1") (pintype "passive"))
    )
    (net (code "38") (name "Net-(F2-P$1)") (class "Default")
      (node (ref "D4") (pin "K") (pinfunction "K_K") (pintype "bidirectional"))
      (node (ref "F2") (pin "1") (pinfunction "P$1_1") (pintype "bidirectional"))
    )
    (net (code "39") (name "Net-(J1-1VCC)") (class "Default")
      (node (ref "D3") (pin "A") (pinfunction "A_A") (pintype "bidirectional"))
      (node (ref "J1") (pin "1") (pinfunction "1VCC_1") (pintype "bidirectional"))
    )
    (net (code "40") (name "Net-(J2-Pad4)") (class "Default")
      (node (ref "J2") (pin "4") (pinfunction "4_4") (pintype "bidirectional"))
      (node (ref "J2") (pin "5") (pinfunction "5_5") (pintype "bidirectional"))
      (node (ref "R63") (pin "2") (pinfunction "2_2") (pintype "passive"))
    )
    (net (code "41") (name "Net-(J2-Pad7)") (class "Default")
      (node (ref "J2") (pin "7") (pinfunction "7_7") (pintype "bidirectional"))
      (node (ref "J2") (pin "8") (pinfunction "8_8") (pintype "bidirectional"))
      (node (ref "R60") (pin "2") (pinfunction "2_2") (pintype "passive"))
    )
    (net (code "42") (name "Net-(L2-2)") (class "Default")
      (node (ref "C9") (pin "2") (pinfunction "2_2") (pintype "passive"))
      (node (ref "L2") (pin "P$2") (pinfunction "2_P$2") (pintype "passive"))
      (node (ref "L3") (pin "OUT2") (pinfunction "2OUT_OUT2") (pintype "bidirectional"))
      (node (ref "R35") (pin "2") (pinfunction "2_2") (pintype "passive"))
    )
    (net (code "43") (name "Net-(L3-1IN)") (class "Default")
      (node (ref "J3") (pin "2A") (pinfunction "2_2A") (pintype "bidirectional"))
      (node (ref "J3") (pin "2B") (pinfunction "2_2B") (pintype "bidirectional"))
      (node (ref "L3") (pin "IN1") (pinfunction "1IN_IN1") (pintype "bidirectional"))
    )
    (net (code "44") (name "Net-(L3-1OUT)") (class "Default")
      (node (ref "C8") (pin "1") (pinfunction "1_1") (pintype "passive"))
      (node (ref "L3") (pin "OUT1") (pinfunction "1OUT_OUT1") (pintype "bidirectional"))
      (node (ref "L5") (pin "P$2") (pinfunction "2_P$2") (pintype "passive"))
      (node (ref "R36") (pin "2") (pinfunction "2_2") (pintype "passive"))
    )
    (net (code "45") (name "Net-(L3-2IN)") (class "Default")
      (node (ref "J3") (pin "1A") (pinfunction "1_1A") (pintype "bidirectional"))
      (node (ref "J3") (pin "1B") (pinfunction "1_1B") (pintype "bidirectional"))
      (node (ref "L3") (pin "IN2") (pinfunction "2IN_IN2") (pintype "bidirectional"))
    )
    (net (code "46") (name "Net-(L4-1IN)") (class "Default")
      (node (ref "J4") (pin "2A") (pinfunction "2_2A") (pintype "bidirectional"))
      (node (ref "J4") (pin "2B") (pinfunction "2_2B") (pintype "bidirectional"))
      (node (ref "L4") (pin "IN1") (pinfunction "1IN_IN1") (pintype "bidirectional"))
    )
    (net (code "47") (name "Net-(L4-1OUT)") (class "Default")
      (node (ref "C48") (pin "1") (pinfunction "1_1") (pintype "passive"))
      (node (ref "D4") (pin "A") (pinfunction "A_A") (pintype "bidirectional"))
      (node (ref "L4") (pin "OUT1") (pinfunction "1OUT_OUT1") (pintype "bidirectional"))
    )
    (net (code "48") (name "Net-(L4-2IN)") (class "Default")
      (node (ref "J4") (pin "1A") (pinfunction "1_1A") (pintype "bidirectional"))
      (node (ref "J4") (pin "1B") (pinfunction "1_1B") (pintype "bidirectional"))
      (node (ref "L4") (pin "IN2") (pinfunction "2IN_IN2") (pintype "bidirectional"))
    )
    (net (code "49") (name "Net-(T1-2)") (class "Default")
      (node (ref "R25") (pin "2") (pinfunction "2_2") (pintype "passive"))
      (node (ref "T1") (pin "6") (pinfunction "2_6") (pintype "bidirectional"))
    )
    (net (code "50") (name "Net-(T1-3)") (class "Default")
      (node (ref "C9") (pin "1") (pinfunction "1_1") (pintype "passive"))
      (node (ref "T1") (pin "2") (pinfunction "3_2") (pintype "bidirectional"))
    )
    (net (code "51") (name "Net-(T1-5)") (class "Default")
      (node (ref "C16") (pin "2") (pinfunction "2_2") (pintype "passive"))
      (node (ref "T1") (pin "3") (pinfunction "5_3") (pintype "bidirectional"))
    )
    (net (code "52") (name "Net-(T4-1C)") (class "Default")
      (node (ref "R32") (pin "1") (pinfunction "1_1") (pintype "passive"))
      (node (ref "T4") (pin "15") (pinfunction "1C_15") (pintype "bidirectional"))
    )
    (net (code "53") (name "Net-(T4-2C)") (class "Default")
      (node (ref "R33") (pin "1") (pinfunction "1_1") (pintype "passive"))
      (node (ref "T4") (pin "10") (pinfunction "2C_10") (pintype "bidirectional"))
    )
    (net (code "54") (name "Net-(U1-PWDN{slash}INT)") (class "Default")
      (node (ref "R31") (pin "1") (pinfunction "1_1") (pintype "passive"))
      (node (ref "U1") (pin "21") (pinfunction "PWDN/INT_21") (pintype "bidirectional"))
    )
    (net (code "55") (name "Net-(U1-RX+)") (class "Default")
      (node (ref "R20") (pin "2") (pinfunction "2_2") (pintype "passive"))
      (node (ref "U1") (pin "5") (pinfunction "RX+_5") (pintype "bidirectional"))
    )
    (net (code "56") (name "Net-(U1-RX-)") (class "Default")
      (node (ref "R21") (pin "2") (pinfunction "2_2") (pintype "passive"))
      (node (ref "U1") (pin "6") (pinfunction "RX-_6") (pintype "bidirectional"))
    )
    (net (code "57") (name "Net-(U1-TX+)") (class "Default")
      (node (ref "R19") (pin "2") (pinfunction "2_2") (pintype "passive"))
      (node (ref "U1") (pin "4") (pinfunction "TX+_4") (pintype "bidirectional"))
    )
    (net (code "58") (name "Net-(U1-TX-)") (class "Default")
      (node (ref "R23") (pin "2") (pinfunction "2_2") (pintype "passive"))
      (node (ref "U1") (pin "7") (pinfunction "TX-_7") (pintype "bidirectional"))
    )
    (net (code "59") (name "Net-(U1-XI{slash}50M)") (class "Default")
      (node (ref "R45") (pin "2") (pinfunction "2_2") (pintype "passive"))
      (node (ref "U1") (pin "10") (pinfunction "XI/50M_10") (pintype "bidirectional"))
    )
    (net (code "60") (name "Net-(U2-RBIAS)") (class "Default")
      (node (ref "R37") (pin "2") (pinfunction "2_2") (pintype "passive"))
      (node (ref "U2") (pin "16") (pinfunction "RBIAS_16") (pintype "bidirectional"))
    )
    (net (code "61") (name "Net-(U2-RX_CLK)") (class "Default")
      (node (ref "R14") (pin "2") (pinfunction "2_2") (pintype "passive"))
      (node (ref "U2") (pin "25") (pinfunction "RX_CLK_25") (pintype "bidirectional"))
    )
    (net (code "62") (name "Net-(U2-RX_DV{slash}RX_CTRL)") (class "Default")
      (node (ref "R12") (pin "2") (pinfunction "2_2") (pintype "passive"))
      (node (ref "U2") (pin "26") (pinfunction "RX_DV/RX_CTRL_26") (pintype "bidirectional"))
    )
    (net (code "63") (name "Net-(U2-TX_D0)") (class "Default")
      (node (ref "R3") (pin "2") (pinfunction "2_2") (pintype "passive"))
      (node (ref "U2") (pin "4") (pinfunction "TX_D0_4") (pintype "bidirectional"))
    )
    (net (code "64") (name "Net-(U2-TX_D1)") (class "Default")
      (node (ref "R4") (pin "2") (pinfunction "2_2") (pintype "passive"))
      (node (ref "U2") (pin "5") (pinfunction "TX_D1_5") (pintype "bidirectional"))
    )
    (net (code "65") (name "Net-(U2-TX_D2)") (class "Default")
      (node (ref "R5") (pin "2") (pinfunction "2_2") (pintype "passive"))
      (node (ref "U2") (pin "6") (pinfunction "TX_D2_6") (pintype "bidirectional"))
    )
    (net (code "66") (name "Net-(U2-TX_D3)") (class "Default")
      (node (ref "R6") (pin "2") (pinfunction "2_2") (pintype "passive"))
      (node (ref "U2") (pin "7") (pinfunction "TX_D3_7") (pintype "bidirectional"))
    )
    (net (code "67") (name "Net-(U2-TX_EN{slash}TX_CTRL)") (class "Default")
      (node (ref "R11") (pin "2") (pinfunction "2_2") (pintype "passive"))
      (node (ref "U2") (pin "3") (pinfunction "TX_EN/TX_CTRL_3") (pintype "bidirectional"))
    )
    (net (code "68") (name "Net-(U2-XI)") (class "Default")
      (node (ref "R41") (pin "2") (pinfunction "2_2") (pintype "passive"))
      (node (ref "R44") (pin "2") (pinfunction "2_2") (pintype "passive"))
      (node (ref "U2") (pin "23") (pinfunction "XI_23") (pintype "bidirectional"))
    )
    (net (code "69") (name "Net-(U2-~{INT{slash}PWDN})") (class "Default")
      (node (ref "R39") (pin "1") (pinfunction "1_1") (pintype "passive"))
      (node (ref "U2") (pin "8") (pinfunction "~{INT/PWDN}_8") (pintype "bidirectional"))
    )
    (net (code "70") (name "Net-(U3-OUT)") (class "Default")
      (node (ref "R44") (pin "1") (pinfunction "1_1") (pintype "passive"))
      (node (ref "R45") (pin "1") (pinfunction "1_1") (pintype "passive"))
      (node (ref "U3") (pin "3") (pinfunction "OUT_3") (pintype "bidirectional"))
    )
    (net (code "71") (name "Net-(U4-BOOT)") (class "Default")
      (node (ref "C54") (pin "1") (pinfunction "1_1") (pintype "passive"))
      (node (ref "U4") (pin "7") (pinfunction "BOOT_7") (pintype "bidirectional"))
    )
    (net (code "72") (name "Net-(U4-EN)") (class "Default")
      (node (ref "R62") (pin "2") (pinfunction "2_2") (pintype "passive"))
      (node (ref "R66") (pin "1") (pinfunction "1_1") (pintype "passive"))
      (node (ref "U4") (pin "2") (pinfunction "EN_2") (pintype "bidirectional"))
    )
    (net (code "73") (name "Net-(U4-FB)") (class "Default")
      (node (ref "R68") (pin "1") (pinfunction "1_1") (pintype "passive"))
      (node (ref "R69") (pin "2") (pinfunction "2_2") (pintype "passive"))
      (node (ref "U4") (pin "5") (pinfunction "FB_5") (pintype "bidirectional"))
    )
    (net (code "74") (name "Net-(U4-RT)") (class "Default")
      (node (ref "R67") (pin "2") (pinfunction "2_2") (pintype "passive"))
      (node (ref "U4") (pin "4") (pinfunction "RT_4") (pintype "bidirectional"))
    )
    (net (code "75") (name "Net-(U4-SW)") (class "Default")
      (node (ref "C54") (pin "2") (pinfunction "2_2") (pintype "passive"))
      (node (ref "L6") (pin "P$2") (pinfunction "P$2_P$2") (pintype "bidirectional"))
      (node (ref "U4") (pin "8") (pinfunction "SW_8") (pintype "bidirectional"))
    )
    (net (code "76") (name "Net-(U4-VIN)") (class "Default")
      (node (ref "C17") (pin "1") (pinfunction "1_1") (pintype "passive"))
      (node (ref "C38") (pin "1") (pinfunction "1_1") (pintype "passive"))
      (node (ref "C39") (pin "1") (pinfunction "1_1") (pintype "passive"))
      (node (ref "C40") (pin "1") (pinfunction "1_1") (pintype "passive"))
      (node (ref "C41") (pin "1") (pinfunction "1_1") (pintype "passive"))
      (node (ref "C42") (pin "1") (pinfunction "1_1") (pintype "passive"))
      (node (ref "C43") (pin "1") (pinfunction "1_1") (pintype "passive"))
      (node (ref "C44") (pin "1") (pinfunction "1_1") (pintype "passive"))
      (node (ref "C45") (pin "1") (pinfunction "1_1") (pintype "passive"))
      (node (ref "C46") (pin "1") (pinfunction "1_1") (pintype "passive"))
      (node (ref "C50") (pin "1") (pinfunction "1_1") (pintype "passive"))
      (node (ref "C51") (pin "1") (pinfunction "1_1") (pintype "passive"))
      (node (ref "C52") (pin "1") (pinfunction "1_1") (pintype "passive"))
      (node (ref "R64") (pin "2") (pinfunction "2_2") (pintype "passive"))
      (node (ref "R66") (pin "2") (pinfunction "2_2") (pintype "passive"))
      (node (ref "U4") (pin "3") (pinfunction "VIN_3") (pintype "bidirectional"))
    )
    (net (code "77") (name "RST_N") (class "Default")
      (node (ref "U4") (pin "6") (pinfunction "PG_6") (pintype "bidirectional"))
    )
    (net (code "78") (name "RTN") (class "Default")
      (node (ref "D5") (pin "A") (pinfunction "A_A") (pintype "bidirectional"))
      (node (ref "D6") (pin "A") (pinfunction "A_A") (pintype "bidirectional"))
      (node (ref "JP2") (pin "1") (pinfunction "1_1") (pintype "passive"))
    )
    (net (code "79") (name "RX_CLK-1") (class "Default")
      (node (ref "R13") (pin "1") (pinfunction "1_1") (pintype "passive"))
      (node (ref "U1") (pin "19") (pinfunction "RX_CLK/50M_RMII_19") (pintype "bidirectional"))
    )
    (net (code "80") (name "RX_D0-1") (class "Default")
      (node (ref "R3") (pin "1") (pinfunction "1_1") (pintype "passive"))
      (node (ref "U1") (pin "16") (pinfunction "RX_D0_16") (pintype "bidirectional"))
    )
    (net (code "81") (name "RX_D0-2") (class "Default")
      (node (ref "R49") (pin "2") (pinfunction "2_2") (pintype "passive"))
      (node (ref "R53") (pin "1") (pinfunction "1_1") (pintype "passive"))
      (node (ref "R7") (pin "2") (pinfunction "2_2") (pintype "passive"))
      (node (ref "U2") (pin "30") (pinfunction "RX_D0_30") (pintype "bidirectional"))
    )
    (net (code "82") (name "RX_D1-1") (class "Default")
      (node (ref "R29") (pin "1") (pinfunction "1_1") (pintype "passive"))
      (node (ref "R4") (pin "1") (pinfunction "1_1") (pintype "passive"))
      (node (ref "U1") (pin "15") (pinfunction "RX_D1_15") (pintype "bidirectional"))
    )
    (net (code "83") (name "RX_D1-2") (class "Default")
      (node (ref "R47") (pin "1") (pinfunction "1_1") (pintype "passive"))
      (node (ref "R8") (pin "2") (pinfunction "2_2") (pintype "passive"))
      (node (ref "U2") (pin "31") (pinfunction "RX_D1_31") (pintype "bidirectional"))
    )
    (net (code "84") (name "RX_D2-1") (class "Default")
      (node (ref "R30") (pin "1") (pinfunction "1_1") (pintype "passive"))
      (node (ref "R5") (pin "1") (pinfunction "1_1") (pintype "passive"))
      (node (ref "U1") (pin "14") (pinfunction "RX_D2_14") (pintype "bidirectional"))
    )
    (net (code "85") (name "RX_D2-2") (class "Default")
      (node (ref "R9") (pin "2") (pinfunction "2_2") (pintype "passive"))
      (node (ref "U2") (pin "32") (pinfunction "RX_D2_32") (pintype "bidirectional"))
    )
    (net (code "86") (name "RX_D3-1") (class "Default")
      (node (ref "R6") (pin "1") (pinfunction "1_1") (pintype "passive"))
      (node (ref "U1") (pin "13") (pinfunction "RX_D3_13") (pintype "bidirectional"))
    )
    (net (code "87") (name "RX_D3-2") (class "Default")
      (node (ref "R10") (pin "2") (pinfunction "2_2") (pintype "passive"))
      (node (ref "U2") (pin "1") (pinfunction "RX_D3_1") (pintype "bidirectional"))
    )
    (net (code "88") (name "RX_DV-1") (class "Default")
      (node (ref "R11") (pin "1") (pinfunction "1_1") (pintype "passive"))
      (node (ref "R27") (pin "1") (pinfunction "1_1") (pintype "passive"))
      (node (ref "U1") (pin "18") (pinfunction "RX_DV/CRS_DV_18") (pintype "bidirectional"))
    )
    (net (code "89") (name "RX_ER-1") (class "Default")
      (node (ref "U1") (pin "20") (pinfunction "RX_ER_20") (pintype "bidirectional"))
    )
    (net (code "90") (name "RX_ER-2") (class "Default")
      (node (ref "R51") (pin "1") (pinfunction "1_1") (pintype "passive"))
      (node (ref "R52") (pin "2") (pinfunction "2_2") (pintype "passive"))
      (node (ref "U2") (pin "28") (pinfunction "RX_ER_28") (pintype "bidirectional"))
    )
    (net (code "91") (name "RX_N") (class "Default")
      (node (ref "J2") (pin "2") (pinfunction "2_2") (pintype "bidirectional"))
      (node (ref "T4") (pin "9") (pinfunction "2N_9") (pintype "bidirectional"))
    )
    (net (code "92") (name "RX_P") (class "Default")
      (node (ref "J2") (pin "1") (pinfunction "1_1") (pintype "bidirectional"))
      (node (ref "T4") (pin "11") (pinfunction "2P_11") (pintype "bidirectional"))
    )
    (net (code "93") (name "TCT") (class "Default")
      (node (ref "C29") (pin "P$1") (pinfunction "1_P$1") (pintype "passive"))
      (node (ref "C31") (pin "P$1") (pinfunction "1_P$1") (pintype "passive"))
      (node (ref "C32") (pin "P$1") (pinfunction "1_P$1") (pintype "passive"))
      (node (ref "C33") (pin "P$1") (pinfunction "1_P$1") (pintype "passive"))
      (node (ref "C34") (pin "P$1") (pinfunction "1_P$1") (pintype "passive"))
      (node (ref "C35") (pin "P$1") (pinfunction "1_P$1") (pintype "passive"))
      (node (ref "C36") (pin "P$1") (pinfunction "1_P$1") (pintype "passive"))
      (node (ref "C58") (pin "P$1") (pinfunction "1_P$1") (pintype "passive"))
      (node (ref "D1") (pin "3") (pinfunction "VCC_3") (pintype "bidirectional"))
      (node (ref "D2") (pin "3") (pinfunction "VCC_3") (pintype "bidirectional"))
      (node (ref "R15") (pin "1") (pinfunction "1_1") (pintype "passive"))
      (node (ref "R16") (pin "2") (pinfunction "2_2") (pintype "passive"))
      (node (ref "R18") (pin "1") (pinfunction "1_1") (pintype "passive"))
      (node (ref "R56") (pin "2") (pinfunction "2_2") (pintype "passive"))
      (node (ref "R61") (pin "1") (pinfunction "1_1") (pintype "passive"))
      (node (ref "T4") (pin "2") (pinfunction "1C_PHY_2") (pintype "bidirectional"))
      (node (ref "T4") (pin "7") (pinfunction "2C_PHY_7") (pintype "bidirectional"))
    )
    (net (code "94") (name "TX_CLK-1") (class "Default")
      (node (ref "R59") (pin "1") (pinfunction "1_1") (pintype "passive"))
      (node (ref "U1") (pin "22") (pinfunction "TX_CLK_22") (pintype "bidirectional"))
      (node (ref "U5") (pin "4") (pinfunction "OUT_4") (pintype "bidirectional"))
    )
    (net (code "95") (name "TX_CLK-1_RC") (class "Default")
      (node (ref "C30") (pin "P$1") (pinfunction "1_P$1") (pintype "passive"))
      (node (ref "R14") (pin "1") (pinfunction "1_1") (pintype "passive"))
      (node (ref "R59") (pin "2") (pinfunction "2_2") (pintype "passive"))
      (node (ref "U5") (pin "2") (pinfunction "IN_2") (pintype "bidirectional"))
    )
    (net (code "96") (name "TX_CLK-2") (class "Default")
      (node (ref "R41") (pin "1") (pinfunction "1_1") (pintype "passive"))
      (node (ref "R58") (pin "2") (pinfunction "2_2") (pintype "passive"))
      (node (ref "U2") (pin "2") (pinfunction "TX_CLK_2") (pintype "bidirectional"))
      (node (ref "U6") (pin "4") (pinfunction "OUT_4") (pintype "bidirectional"))
    )
    (net (code "97") (name "TX_CLK-2_RC") (class "Default")
      (node (ref "C28") (pin "P$1") (pinfunction "1_P$1") (pintype "passive"))
      (node (ref "R13") (pin "2") (pinfunction "2_2") (pintype "passive"))
      (node (ref "R58") (pin "1") (pinfunction "1_1") (pintype "passive"))
      (node (ref "U6") (pin "2") (pinfunction "IN_2") (pintype "bidirectional"))
    )
    (net (code "98") (name "TX_D0-1") (class "Default")
      (node (ref "R7") (pin "1") (pinfunction "1_1") (pintype "passive"))
      (node (ref "U1") (pin "24") (pinfunction "TX_D0_24") (pintype "bidirectional"))
    )
    (net (code "99") (name "TX_D1-1") (class "Default")
      (node (ref "R8") (pin "1") (pinfunction "1_1") (pintype "passive"))
      (node (ref "U1") (pin "25") (pinfunction "TX_D1_25") (pintype "bidirectional"))
    )
    (net (code "100") (name "TX_D2-1") (class "Default")
      (node (ref "R9") (pin "1") (pinfunction "1_1") (pintype "passive"))
      (node (ref "U1") (pin "26") (pinfunction "TX_D2_26") (pintype "bidirectional"))
    )
    (net (code "101") (name "TX_D3-1") (class "Default")
      (node (ref "R10") (pin "1") (pinfunction "1_1") (pintype "passive"))
      (node (ref "U1") (pin "27") (pinfunction "TX_D3_27") (pintype "bidirectional"))
    )
    (net (code "102") (name "TX_EN-1") (class "Default")
      (node (ref "R12") (pin "1") (pinfunction "1_1") (pintype "passive"))
      (node (ref "U1") (pin "23") (pinfunction "TX_EN_23") (pintype "bidirectional"))
    )
    (net (code "103") (name "TX_N") (class "Default")
      (node (ref "J2") (pin "6") (pinfunction "6_6") (pintype "bidirectional"))
      (node (ref "T4") (pin "14") (pinfunction "1N_14") (pintype "bidirectional"))
    )
    (net (code "104") (name "TX_P") (class "Default")
      (node (ref "J2") (pin "3") (pinfunction "3_3") (pintype "bidirectional"))
      (node (ref "T4") (pin "16") (pinfunction "1P_16") (pintype "bidirectional"))
    )
    (net (code "105") (name "V+") (class "Default")
      (node (ref "CR4") (pin "C") (pinfunction "K_C") (pintype "bidirectional"))
      (node (ref "D3") (pin "K") (pinfunction "K_K") (pintype "bidirectional"))
      (node (ref "F1") (pin "2") (pinfunction "P$2_2") (pintype "bidirectional"))
      (node (ref "F2") (pin "2") (pinfunction "P$2_2") (pintype "bidirectional"))
      (node (ref "R64") (pin "1") (pinfunction "1_1") (pintype "passive"))
      (node (ref "TP4") (pin "P$1") (pinfunction "P$1_P$1") (pintype "bidirectional"))
    )
    (net (code "106") (name "V+F") (class "Default")
      (node (ref "F1") (pin "1") (pinfunction "P$1_1") (pintype "bidirectional"))
      (node (ref "JP2") (pin "4") (pinfunction "4_4") (pintype "passive"))
    )
    (net (code "107") (name "VIN") (class "Default")
      (node (ref "D7") (pin "K") (pinfunction "K_K") (pintype "bidirectional"))
      (node (ref "D8") (pin "K") (pinfunction "K_K") (pintype "bidirectional"))
      (node (ref "JP2") (pin "2") (pinfunction "2_2") (pintype "passive"))
    )
    (net (code "108") (name "unconnected-(J1-2DM-Pad2)") (class "Default")
      (node (ref "J1") (pin "2") (pinfunction "2DM_2") (pintype "bidirectional"))
    )
    (net (code "109") (name "unconnected-(J1-3DP-Pad3)") (class "Default")
      (node (ref "J1") (pin "3") (pinfunction "3DP_3") (pintype "bidirectional"))
    )
    (net (code "110") (name "unconnected-(J1-4ID-Pad4)") (class "Default")
      (node (ref "J1") (pin "4") (pinfunction "4ID_4") (pintype "bidirectional"))
    )
    (net (code "111") (name "unconnected-(U1-XO-Pad9)") (class "Default")
      (node (ref "U1") (pin "9") (pinfunction "XO_9") (pintype "bidirectional"))
    )
    (net (code "112") (name "unconnected-(U2-COL{slash}GPIO2-Pad29)") (class "Default")
      (node (ref "U2") (pin "29") (pinfunction "COL/GPIO2_29") (pintype "bidirectional"))
    )
    (net (code "113") (name "unconnected-(U2-LED1{slash}GPIO1-Pad24)") (class "Default")
      (node (ref "U2") (pin "24") (pinfunction "LED1/GPIO1_24") (pintype "bidirectional"))
    )
    (net (code "114") (name "unconnected-(U2-NC1-Pad13)") (class "Default")
      (node (ref "U2") (pin "13") (pinfunction "NC1_13") (pintype "bidirectional"))
    )
    (net (code "115") (name "unconnected-(U2-NC2-Pad15)") (class "Default")
      (node (ref "U2") (pin "15") (pinfunction "NC2_15") (pintype "bidirectional"))
    )
    (net (code "116") (name "unconnected-(U2-XO-Pad22)") (class "Default")
      (node (ref "U2") (pin "22") (pinfunction "XO_22") (pintype "bidirectional"))
    )
    (net (code "117") (name "unconnected-(U3-NC-Pad1)") (class "Default")
      (node (ref "U3") (pin "1") (pinfunction "NC_1") (pintype "bidirectional"))
    )
    (net (code "118") (name "~{RST}") (class "Default")
      (node (ref "C61") (pin "P$1") (pinfunction "1_P$1") (pintype "passive"))
      (node (ref "JP1") (pin "2") (pinfunction "2_2") (pintype "passive"))
      (node (ref "R40") (pin "1") (pinfunction "1_1") (pintype "passive"))
      (node (ref "U1") (pin "31") (pinfunction "~{RST_N}_31") (pintype "bidirectional"))
      (node (ref "U2") (pin "18") (pinfunction "~{RESET\\}_18") (pintype "bidirectional"))
    )
  )
)
